# Proto3-schematic_v1.net
KiCad netlist of a schematic drawn in EAGLE
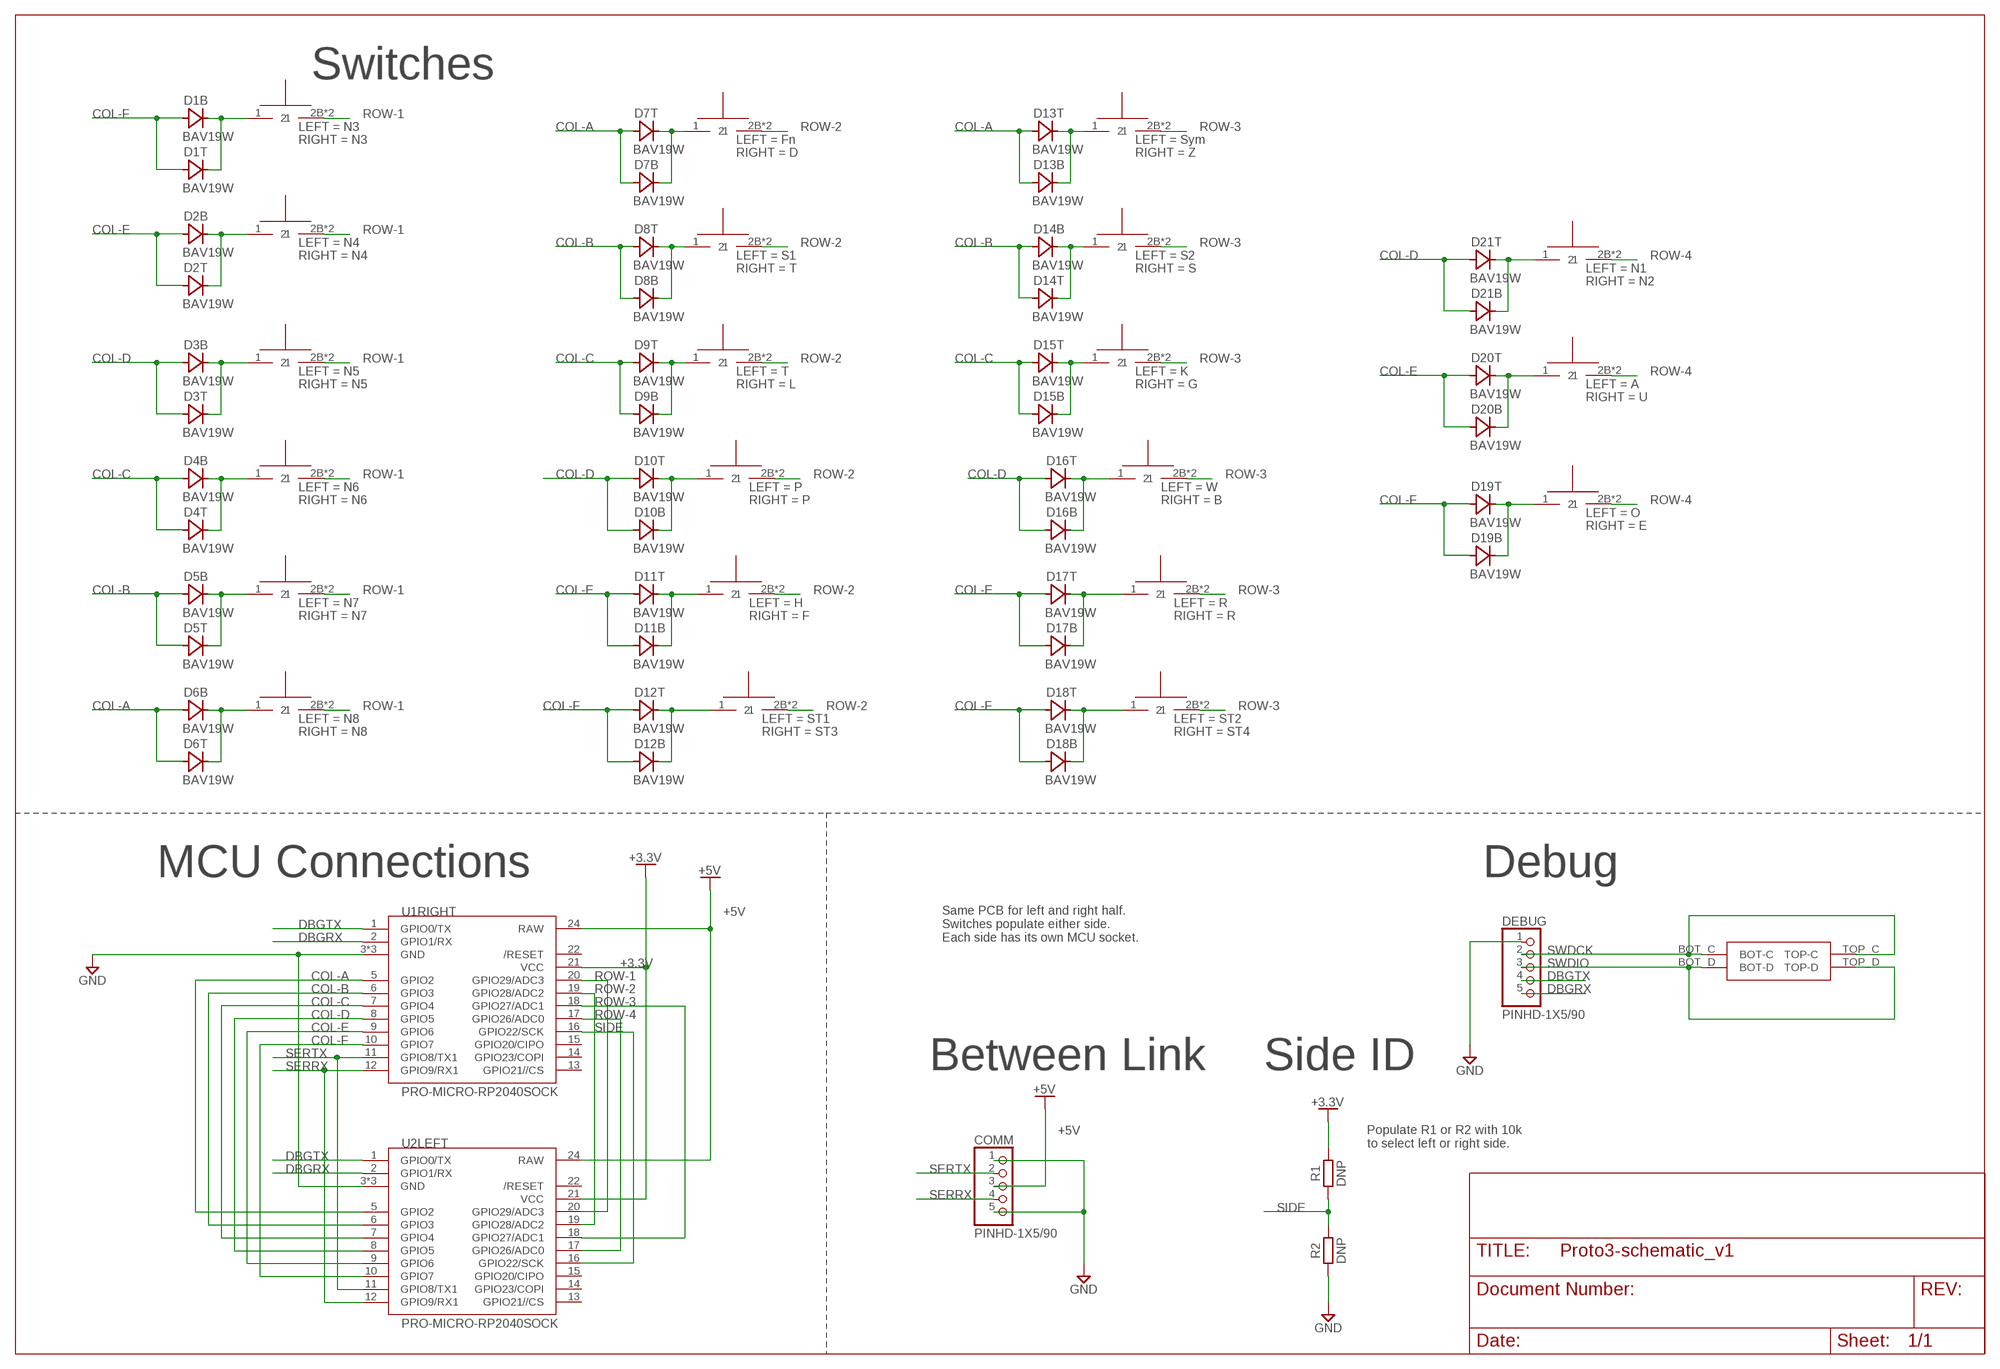
[diagram p0: schematic, sheet 1]

(export (version "E")
  (design (tool "Eeschema 10.0.6"))
  (components
    (comp (ref "COMM")
      (value "PINHD-1X5/90")
      (footprint "eagle-import:1X05_90")
      (libsource (lib "eagle-import") (part "PINHD-1X5/90"))
    )
    (comp (ref "D1B")
      (value "BAV19W")
      (footprint "eagle-import:SOD123")
      (libsource (lib "eagle-import") (part "BAV19W"))
    )
    (comp (ref "D1T")
      (value "BAV19W")
      (footprint "eagle-import:SOD123")
      (libsource (lib "eagle-import") (part "BAV19W"))
    )
    (comp (ref "D2B")
      (value "BAV19W")
      (footprint "eagle-import:SOD123")
      (libsource (lib "eagle-import") (part "BAV19W"))
    )
    (comp (ref "D2T")
      (value "BAV19W")
      (footprint "eagle-import:SOD123")
      (libsource (lib "eagle-import") (part "BAV19W"))
    )
    (comp (ref "D3B")
      (value "BAV19W")
      (footprint "eagle-import:SOD123")
      (libsource (lib "eagle-import") (part "BAV19W"))
    )
    (comp (ref "D3T")
      (value "BAV19W")
      (footprint "eagle-import:SOD123")
      (libsource (lib "eagle-import") (part "BAV19W"))
    )
    (comp (ref "D4B")
      (value "BAV19W")
      (footprint "eagle-import:SOD123")
      (libsource (lib "eagle-import") (part "BAV19W"))
    )
    (comp (ref "D4T")
      (value "BAV19W")
      (footprint "eagle-import:SOD123")
      (libsource (lib "eagle-import") (part "BAV19W"))
    )
    (comp (ref "D5B")
      (value "BAV19W")
      (footprint "eagle-import:SOD123")
      (libsource (lib "eagle-import") (part "BAV19W"))
    )
    (comp (ref "D5T")
      (value "BAV19W")
      (footprint "eagle-import:SOD123")
      (libsource (lib "eagle-import") (part "BAV19W"))
    )
    (comp (ref "D6B")
      (value "BAV19W")
      (footprint "eagle-import:SOD123")
      (libsource (lib "eagle-import") (part "BAV19W"))
    )
    (comp (ref "D6T")
      (value "BAV19W")
      (footprint "eagle-import:SOD123")
      (libsource (lib "eagle-import") (part "BAV19W"))
    )
    (comp (ref "D7B")
      (value "BAV19W")
      (footprint "eagle-import:SOD123")
      (libsource (lib "eagle-import") (part "BAV19W"))
    )
    (comp (ref "D7T")
      (value "BAV19W")
      (footprint "eagle-import:SOD123")
      (libsource (lib "eagle-import") (part "BAV19W"))
    )
    (comp (ref "D8B")
      (value "BAV19W")
      (footprint "eagle-import:SOD123")
      (libsource (lib "eagle-import") (part "BAV19W"))
    )
    (comp (ref "D8T")
      (value "BAV19W")
      (footprint "eagle-import:SOD123")
      (libsource (lib "eagle-import") (part "BAV19W"))
    )
    (comp (ref "D9B")
      (value "BAV19W")
      (footprint "eagle-import:SOD123")
      (libsource (lib "eagle-import") (part "BAV19W"))
    )
    (comp (ref "D9T")
      (value "BAV19W")
      (footprint "eagle-import:SOD123")
      (libsource (lib "eagle-import") (part "BAV19W"))
    )
    (comp (ref "D10B")
      (value "BAV19W")
      (footprint "eagle-import:SOD123")
      (libsource (lib "eagle-import") (part "BAV19W"))
    )
    (comp (ref "D10T")
      (value "BAV19W")
      (footprint "eagle-import:SOD123")
      (libsource (lib "eagle-import") (part "BAV19W"))
    )
    (comp (ref "D11B")
      (value "BAV19W")
      (footprint "eagle-import:SOD123")
      (libsource (lib "eagle-import") (part "BAV19W"))
    )
    (comp (ref "D11T")
      (value "BAV19W")
      (footprint "eagle-import:SOD123")
      (libsource (lib "eagle-import") (part "BAV19W"))
    )
    (comp (ref "D12B")
      (value "BAV19W")
      (footprint "eagle-import:SOD123")
      (libsource (lib "eagle-import") (part "BAV19W"))
    )
    (comp (ref "D12T")
      (value "BAV19W")
      (footprint "eagle-import:SOD123")
      (libsource (lib "eagle-import") (part "BAV19W"))
    )
    (comp (ref "D13B")
      (value "BAV19W")
      (footprint "eagle-import:SOD123")
      (libsource (lib "eagle-import") (part "BAV19W"))
    )
    (comp (ref "D13T")
      (value "BAV19W")
      (footprint "eagle-import:SOD123")
      (libsource (lib "eagle-import") (part "BAV19W"))
    )
    (comp (ref "D14B")
      (value "BAV19W")
      (footprint "eagle-import:SOD123")
      (libsource (lib "eagle-import") (part "BAV19W"))
    )
    (comp (ref "D14T")
      (value "BAV19W")
      (footprint "eagle-import:SOD123")
      (libsource (lib "eagle-import") (part "BAV19W"))
    )
    (comp (ref "D15B")
      (value "BAV19W")
      (footprint "eagle-import:SOD123")
      (libsource (lib "eagle-import") (part "BAV19W"))
    )
    (comp (ref "D15T")
      (value "BAV19W")
      (footprint "eagle-import:SOD123")
      (libsource (lib "eagle-import") (part "BAV19W"))
    )
    (comp (ref "D16B")
      (value "BAV19W")
      (footprint "eagle-import:SOD123")
      (libsource (lib "eagle-import") (part "BAV19W"))
    )
    (comp (ref "D16T")
      (value "BAV19W")
      (footprint "eagle-import:SOD123")
      (libsource (lib "eagle-import") (part "BAV19W"))
    )
    (comp (ref "D17B")
      (value "BAV19W")
      (footprint "eagle-import:SOD123")
      (libsource (lib "eagle-import") (part "BAV19W"))
    )
    (comp (ref "D17T")
      (value "BAV19W")
      (footprint "eagle-import:SOD123")
      (libsource (lib "eagle-import") (part "BAV19W"))
    )
    (comp (ref "D18B")
      (value "BAV19W")
      (footprint "eagle-import:SOD123")
      (libsource (lib "eagle-import") (part "BAV19W"))
    )
    (comp (ref "D18T")
      (value "BAV19W")
      (footprint "eagle-import:SOD123")
      (libsource (lib "eagle-import") (part "BAV19W"))
    )
    (comp (ref "D19B")
      (value "BAV19W")
      (footprint "eagle-import:SOD123")
      (libsource (lib "eagle-import") (part "BAV19W"))
    )
    (comp (ref "D19T")
      (value "BAV19W")
      (footprint "eagle-import:SOD123")
      (libsource (lib "eagle-import") (part "BAV19W"))
    )
    (comp (ref "D20B")
      (value "BAV19W")
      (footprint "eagle-import:SOD123")
      (libsource (lib "eagle-import") (part "BAV19W"))
    )
    (comp (ref "D20T")
      (value "BAV19W")
      (footprint "eagle-import:SOD123")
      (libsource (lib "eagle-import") (part "BAV19W"))
    )
    (comp (ref "D21B")
      (value "BAV19W")
      (footprint "eagle-import:SOD123")
      (libsource (lib "eagle-import") (part "BAV19W"))
    )
    (comp (ref "D21T")
      (value "BAV19W")
      (footprint "eagle-import:SOD123")
      (libsource (lib "eagle-import") (part "BAV19W"))
    )
    (comp (ref "DEBUG")
      (value "PINHD-1X5/90")
      (footprint "eagle-import:1X05_90")
      (libsource (lib "eagle-import") (part "PINHD-1X5/90"))
    )
    (comp (ref "R1")
      (value "DNP")
      (footprint "eagle-import:RESAD724W46L381D178B")
      (libsource (lib "eagle-import") (part "RAXIAL-7.2MM-PITCH_"))
    )
    (comp (ref "R2")
      (value "DNP")
      (footprint "eagle-import:RESAD724W46L381D178B")
      (libsource (lib "eagle-import") (part "RAXIAL-7.2MM-PITCH_"))
    )
    (comp (ref "SW-LFN-RD")
      (value "PG1350-PINKA")
      (footprint "eagle-import:PG1350")
      (fields (field (name "LEFT") "Fn") (field (name "RIGHT") "D"))
      (libsource (lib "eagle-import") (part "PG1350-PINKA"))
    )
    (comp (ref "SW-LFN-RD1")
      (value "PG1350-PINKA")
      (footprint "eagle-import:PG1350")
      (fields (field (name "LEFT") "Sym") (field (name "RIGHT") "Z"))
      (libsource (lib "eagle-import") (part "PG1350-PINKA"))
    )
    (comp (ref "SW-LFN-RD2")
      (value "PG1350-PINKA")
      (footprint "eagle-import:PG1350")
      (fields (field (name "LEFT") "S1") (field (name "RIGHT") "T"))
      (libsource (lib "eagle-import") (part "PG1350-PINKA"))
    )
    (comp (ref "SW-LFN-RD3")
      (value "PG1350-PINKA")
      (footprint "eagle-import:PG1350")
      (fields (field (name "LEFT") "S2") (field (name "RIGHT") "S"))
      (libsource (lib "eagle-import") (part "PG1350-PINKA"))
    )
    (comp (ref "SW-LFN-RD4")
      (value "PG1350-PINKA")
      (footprint "eagle-import:PG1350")
      (fields (field (name "LEFT") "T") (field (name "RIGHT") "L"))
      (libsource (lib "eagle-import") (part "PG1350-PINKA"))
    )
    (comp (ref "SW-LFN-RD5")
      (value "PG1350-PINKA")
      (footprint "eagle-import:PG1350")
      (fields (field (name "LEFT") "K") (field (name "RIGHT") "G"))
      (libsource (lib "eagle-import") (part "PG1350-PINKA"))
    )
    (comp (ref "SW-LFN-RD6")
      (value "PG1350-PINKA")
      (footprint "eagle-import:PG1350")
      (fields (field (name "LEFT") "P") (field (name "RIGHT") "P"))
      (libsource (lib "eagle-import") (part "PG1350-PINKA"))
    )
    (comp (ref "SW-LFN-RD7")
      (value "PG1350-PINKA")
      (footprint "eagle-import:PG1350")
      (fields (field (name "LEFT") "W") (field (name "RIGHT") "B"))
      (libsource (lib "eagle-import") (part "PG1350-PINKA"))
    )
    (comp (ref "SW-LFN-RD8")
      (value "PG1350-PINKA")
      (footprint "eagle-import:PG1350")
      (fields (field (name "LEFT") "H") (field (name "RIGHT") "F"))
      (libsource (lib "eagle-import") (part "PG1350-PINKA"))
    )
    (comp (ref "SW-LFN-RD9")
      (value "PG1350-PINKA")
      (footprint "eagle-import:PG1350")
      (fields (field (name "LEFT") "R") (field (name "RIGHT") "R"))
      (libsource (lib "eagle-import") (part "PG1350-PINKA"))
    )
    (comp (ref "SW-LFN-RD10")
      (value "PG1350-PINKA")
      (footprint "eagle-import:PG1350")
      (fields (field (name "LEFT") "ST1") (field (name "RIGHT") "ST3"))
      (libsource (lib "eagle-import") (part "PG1350-PINKA"))
    )
    (comp (ref "SW-LFN-RD11")
      (value "PG1350-PINKA")
      (footprint "eagle-import:PG1350")
      (fields (field (name "LEFT") "ST2") (field (name "RIGHT") "ST4"))
      (libsource (lib "eagle-import") (part "PG1350-PINKA"))
    )
    (comp (ref "SW-LFN-RD12")
      (value "PG1350-PINKA")
      (footprint "eagle-import:PG1350")
      (fields (field (name "LEFT") "N1") (field (name "RIGHT") "N2"))
      (libsource (lib "eagle-import") (part "PG1350-PINKA"))
    )
    (comp (ref "SW-LFN-RD13")
      (value "PG1350-PINKA")
      (footprint "eagle-import:PG1350")
      (fields (field (name "LEFT") "A") (field (name "RIGHT") "U"))
      (libsource (lib "eagle-import") (part "PG1350-PINKA"))
    )
    (comp (ref "SW-LFN-RD14")
      (value "PG1350-PINKA")
      (footprint "eagle-import:PG1350")
      (fields (field (name "LEFT") "O") (field (name "RIGHT") "E"))
      (libsource (lib "eagle-import") (part "PG1350-PINKA"))
    )
    (comp (ref "SW-LFN-RD15")
      (value "PG1350-PINKA")
      (footprint "eagle-import:PG1350")
      (fields (field (name "LEFT") "N8") (field (name "RIGHT") "N8"))
      (libsource (lib "eagle-import") (part "PG1350-PINKA"))
    )
    (comp (ref "SW-LFN-RD16")
      (value "PG1350-PINKA")
      (footprint "eagle-import:PG1350")
      (fields (field (name "LEFT") "N7") (field (name "RIGHT") "N7"))
      (libsource (lib "eagle-import") (part "PG1350-PINKA"))
    )
    (comp (ref "SW-LFN-RD17")
      (value "PG1350-PINKA")
      (footprint "eagle-import:PG1350")
      (fields (field (name "LEFT") "N6") (field (name "RIGHT") "N6"))
      (libsource (lib "eagle-import") (part "PG1350-PINKA"))
    )
    (comp (ref "SW-LFN-RD18")
      (value "PG1350-PINKA")
      (footprint "eagle-import:PG1350")
      (fields (field (name "LEFT") "N5") (field (name "RIGHT") "N5"))
      (libsource (lib "eagle-import") (part "PG1350-PINKA"))
    )
    (comp (ref "SW-LFN-RD19")
      (value "PG1350-PINKA")
      (footprint "eagle-import:PG1350")
      (fields (field (name "LEFT") "N4") (field (name "RIGHT") "N4"))
      (libsource (lib "eagle-import") (part "PG1350-PINKA"))
    )
    (comp (ref "SW-LFN-RD20")
      (value "PG1350-PINKA")
      (footprint "eagle-import:PG1350")
      (fields (field (name "LEFT") "N3") (field (name "RIGHT") "N3"))
      (libsource (lib "eagle-import") (part "PG1350-PINKA"))
    )
    (comp (ref "U$3")
      (value "SWD-TP-HEADER")
      (footprint "eagle-import:SWD-TP-HEADER")
      (libsource (lib "eagle-import") (part "SWD-TP-HEADER"))
    )
    (comp (ref "U1RIGHT")
      (value "PRO-MICRO-RP2040SOCK")
      (footprint "eagle-import:PRO-MICRO-RP2040-SOCKETED")
      (libsource (lib "eagle-import") (part "PRO-MICRO-RP2040SOCK"))
    )
    (comp (ref "U2LEFT")
      (value "PRO-MICRO-RP2040SOCK")
      (footprint "eagle-import:PRO-MICRO-RP2040-SOCKETED")
      (libsource (lib "eagle-import") (part "PRO-MICRO-RP2040SOCK"))
    )
  )
  (nets
    (net (code "1") (name "+3.3V") (class "Default")
      (node (ref "R1") (pin "2") (pinfunction "2_2") (pintype "passive"))
      (node (ref "U1RIGHT") (pin "21") (pinfunction "VCC_21") (pintype "power_in"))
      (node (ref "U2LEFT") (pin "21") (pinfunction "VCC_21") (pintype "power_in"))
    )
    (net (code "2") (name "+5V") (class "Default")
      (node (ref "COMM") (pin "3") (pinfunction "3_3") (pintype "passive"))
      (node (ref "U1RIGHT") (pin "24") (pinfunction "RAW_24") (pintype "power_in"))
      (node (ref "U2LEFT") (pin "24") (pinfunction "RAW_24") (pintype "power_in"))
    )
    (net (code "3") (name "/COL-A") (class "Default")
      (node (ref "D13B") (pin "A") (pinfunction "A_A") (pintype "passive"))
      (node (ref "D13T") (pin "A") (pinfunction "A_A") (pintype "passive"))
      (node (ref "D6B") (pin "A") (pinfunction "A_A") (pintype "passive"))
      (node (ref "D6T") (pin "A") (pinfunction "A_A") (pintype "passive"))
      (node (ref "D7B") (pin "A") (pinfunction "A_A") (pintype "passive"))
      (node (ref "D7T") (pin "A") (pinfunction "A_A") (pintype "passive"))
      (node (ref "U1RIGHT") (pin "5") (pinfunction "GPIO2_5") (pintype "bidirectional"))
      (node (ref "U2LEFT") (pin "5") (pinfunction "GPIO2_5") (pintype "bidirectional"))
    )
    (net (code "4") (name "/COL-B") (class "Default")
      (node (ref "D14B") (pin "A") (pinfunction "A_A") (pintype "passive"))
      (node (ref "D14T") (pin "A") (pinfunction "A_A") (pintype "passive"))
      (node (ref "D5B") (pin "A") (pinfunction "A_A") (pintype "passive"))
      (node (ref "D5T") (pin "A") (pinfunction "A_A") (pintype "passive"))
      (node (ref "D8B") (pin "A") (pinfunction "A_A") (pintype "passive"))
      (node (ref "D8T") (pin "A") (pinfunction "A_A") (pintype "passive"))
      (node (ref "U1RIGHT") (pin "6") (pinfunction "GPIO3_6") (pintype "bidirectional"))
      (node (ref "U2LEFT") (pin "6") (pinfunction "GPIO3_6") (pintype "bidirectional"))
    )
    (net (code "5") (name "/COL-C") (class "Default")
      (node (ref "D15B") (pin "A") (pinfunction "A_A") (pintype "passive"))
      (node (ref "D15T") (pin "A") (pinfunction "A_A") (pintype "passive"))
      (node (ref "D4B") (pin "A") (pinfunction "A_A") (pintype "passive"))
      (node (ref "D4T") (pin "A") (pinfunction "A_A") (pintype "passive"))
      (node (ref "D9B") (pin "A") (pinfunction "A_A") (pintype "passive"))
      (node (ref "D9T") (pin "A") (pinfunction "A_A") (pintype "passive"))
      (node (ref "U1RIGHT") (pin "7") (pinfunction "GPIO4_7") (pintype "bidirectional"))
      (node (ref "U2LEFT") (pin "7") (pinfunction "GPIO4_7") (pintype "bidirectional"))
    )
    (net (code "6") (name "/COL-D") (class "Default")
      (node (ref "D10B") (pin "A") (pinfunction "A_A") (pintype "passive"))
      (node (ref "D10T") (pin "A") (pinfunction "A_A") (pintype "passive"))
      (node (ref "D16B") (pin "A") (pinfunction "A_A") (pintype "passive"))
      (node (ref "D16T") (pin "A") (pinfunction "A_A") (pintype "passive"))
      (node (ref "D21B") (pin "A") (pinfunction "A_A") (pintype "passive"))
      (node (ref "D21T") (pin "A") (pinfunction "A_A") (pintype "passive"))
      (node (ref "D3B") (pin "A") (pinfunction "A_A") (pintype "passive"))
      (node (ref "D3T") (pin "A") (pinfunction "A_A") (pintype "passive"))
      (node (ref "U1RIGHT") (pin "8") (pinfunction "GPIO5_8") (pintype "bidirectional"))
      (node (ref "U2LEFT") (pin "8") (pinfunction "GPIO5_8") (pintype "bidirectional"))
    )
    (net (code "7") (name "/COL-E") (class "Default")
      (node (ref "D11B") (pin "A") (pinfunction "A_A") (pintype "passive"))
      (node (ref "D11T") (pin "A") (pinfunction "A_A") (pintype "passive"))
      (node (ref "D17B") (pin "A") (pinfunction "A_A") (pintype "passive"))
      (node (ref "D17T") (pin "A") (pinfunction "A_A") (pintype "passive"))
      (node (ref "D20B") (pin "A") (pinfunction "A_A") (pintype "passive"))
      (node (ref "D20T") (pin "A") (pinfunction "A_A") (pintype "passive"))
      (node (ref "D2B") (pin "A") (pinfunction "A_A") (pintype "passive"))
      (node (ref "D2T") (pin "A") (pinfunction "A_A") (pintype "passive"))
      (node (ref "U1RIGHT") (pin "9") (pinfunction "GPIO6_9") (pintype "bidirectional"))
      (node (ref "U2LEFT") (pin "9") (pinfunction "GPIO6_9") (pintype "bidirectional"))
    )
    (net (code "8") (name "/COL-F") (class "Default")
      (node (ref "D12B") (pin "A") (pinfunction "A_A") (pintype "passive"))
      (node (ref "D12T") (pin "A") (pinfunction "A_A") (pintype "passive"))
      (node (ref "D18B") (pin "A") (pinfunction "A_A") (pintype "passive"))
      (node (ref "D18T") (pin "A") (pinfunction "A_A") (pintype "passive"))
      (node (ref "D19B") (pin "A") (pinfunction "A_A") (pintype "passive"))
      (node (ref "D19T") (pin "A") (pinfunction "A_A") (pintype "passive"))
      (node (ref "D1B") (pin "A") (pinfunction "A_A") (pintype "passive"))
      (node (ref "D1T") (pin "A") (pinfunction "A_A") (pintype "passive"))
      (node (ref "U1RIGHT") (pin "10") (pinfunction "GPIO7_10") (pintype "bidirectional"))
      (node (ref "U2LEFT") (pin "10") (pinfunction "GPIO7_10") (pintype "bidirectional"))
    )
    (net (code "9") (name "/DBGRX") (class "Default")
      (node (ref "DEBUG") (pin "5") (pinfunction "5_5") (pintype "passive"))
      (node (ref "U1RIGHT") (pin "2") (pinfunction "GPIO1/RX_2") (pintype "bidirectional"))
      (node (ref "U2LEFT") (pin "2") (pinfunction "GPIO1/RX_2") (pintype "bidirectional"))
    )
    (net (code "10") (name "/DBGTX") (class "Default")
      (node (ref "DEBUG") (pin "4") (pinfunction "4_4") (pintype "passive"))
      (node (ref "U1RIGHT") (pin "1") (pinfunction "GPIO0/TX_1") (pintype "bidirectional"))
      (node (ref "U2LEFT") (pin "1") (pinfunction "GPIO0/TX_1") (pintype "bidirectional"))
    )
    (net (code "11") (name "/ROW-1") (class "Default")
      (node (ref "SW-LFN-RD15") (pin "2B") (pinfunction "2_2B") (pintype "passive"))
      (node (ref "SW-LFN-RD15") (pin "2T") (pinfunction "2_2T") (pintype "passive"))
      (node (ref "SW-LFN-RD16") (pin "2B") (pinfunction "2_2B") (pintype "passive"))
      (node (ref "SW-LFN-RD16") (pin "2T") (pinfunction "2_2T") (pintype "passive"))
      (node (ref "SW-LFN-RD17") (pin "2B") (pinfunction "2_2B") (pintype "passive"))
      (node (ref "SW-LFN-RD17") (pin "2T") (pinfunction "2_2T") (pintype "passive"))
      (node (ref "SW-LFN-RD18") (pin "2B") (pinfunction "2_2B") (pintype "passive"))
      (node (ref "SW-LFN-RD18") (pin "2T") (pinfunction "2_2T") (pintype "passive"))
      (node (ref "SW-LFN-RD19") (pin "2B") (pinfunction "2_2B") (pintype "passive"))
      (node (ref "SW-LFN-RD19") (pin "2T") (pinfunction "2_2T") (pintype "passive"))
      (node (ref "SW-LFN-RD20") (pin "2B") (pinfunction "2_2B") (pintype "passive"))
      (node (ref "SW-LFN-RD20") (pin "2T") (pinfunction "2_2T") (pintype "passive"))
      (node (ref "U1RIGHT") (pin "20") (pinfunction "GPIO29/ADC3_20") (pintype "bidirectional"))
      (node (ref "U2LEFT") (pin "20") (pinfunction "GPIO29/ADC3_20") (pintype "bidirectional"))
    )
    (net (code "12") (name "/ROW-2") (class "Default")
      (node (ref "SW-LFN-RD") (pin "2B") (pinfunction "2_2B") (pintype "passive"))
      (node (ref "SW-LFN-RD") (pin "2T") (pinfunction "2_2T") (pintype "passive"))
      (node (ref "SW-LFN-RD10") (pin "2B") (pinfunction "2_2B") (pintype "passive"))
      (node (ref "SW-LFN-RD10") (pin "2T") (pinfunction "2_2T") (pintype "passive"))
      (node (ref "SW-LFN-RD2") (pin "2B") (pinfunction "2_2B") (pintype "passive"))
      (node (ref "SW-LFN-RD2") (pin "2T") (pinfunction "2_2T") (pintype "passive"))
      (node (ref "SW-LFN-RD4") (pin "2B") (pinfunction "2_2B") (pintype "passive"))
      (node (ref "SW-LFN-RD4") (pin "2T") (pinfunction "2_2T") (pintype "passive"))
      (node (ref "SW-LFN-RD6") (pin "2B") (pinfunction "2_2B") (pintype "passive"))
      (node (ref "SW-LFN-RD6") (pin "2T") (pinfunction "2_2T") (pintype "passive"))
      (node (ref "SW-LFN-RD8") (pin "2B") (pinfunction "2_2B") (pintype "passive"))
      (node (ref "SW-LFN-RD8") (pin "2T") (pinfunction "2_2T") (pintype "passive"))
      (node (ref "U1RIGHT") (pin "19") (pinfunction "GPIO28/ADC2_19") (pintype "bidirectional"))
      (node (ref "U2LEFT") (pin "19") (pinfunction "GPIO28/ADC2_19") (pintype "bidirectional"))
    )
    (net (code "13") (name "/ROW-3") (class "Default")
      (node (ref "SW-LFN-RD1") (pin "2B") (pinfunction "2_2B") (pintype "passive"))
      (node (ref "SW-LFN-RD1") (pin "2T") (pinfunction "2_2T") (pintype "passive"))
      (node (ref "SW-LFN-RD11") (pin "2B") (pinfunction "2_2B") (pintype "passive"))
      (node (ref "SW-LFN-RD11") (pin "2T") (pinfunction "2_2T") (pintype "passive"))
      (node (ref "SW-LFN-RD3") (pin "2B") (pinfunction "2_2B") (pintype "passive"))
      (node (ref "SW-LFN-RD3") (pin "2T") (pinfunction "2_2T") (pintype "passive"))
      (node (ref "SW-LFN-RD5") (pin "2B") (pinfunction "2_2B") (pintype "passive"))
      (node (ref "SW-LFN-RD5") (pin "2T") (pinfunction "2_2T") (pintype "passive"))
      (node (ref "SW-LFN-RD7") (pin "2B") (pinfunction "2_2B") (pintype "passive"))
      (node (ref "SW-LFN-RD7") (pin "2T") (pinfunction "2_2T") (pintype "passive"))
      (node (ref "SW-LFN-RD9") (pin "2B") (pinfunction "2_2B") (pintype "passive"))
      (node (ref "SW-LFN-RD9") (pin "2T") (pinfunction "2_2T") (pintype "passive"))
      (node (ref "U1RIGHT") (pin "18") (pinfunction "GPIO27/ADC1_18") (pintype "bidirectional"))
      (node (ref "U2LEFT") (pin "18") (pinfunction "GPIO27/ADC1_18") (pintype "bidirectional"))
    )
    (net (code "14") (name "/ROW-4") (class "Default")
      (node (ref "SW-LFN-RD12") (pin "2B") (pinfunction "2_2B") (pintype "passive"))
      (node (ref "SW-LFN-RD12") (pin "2T") (pinfunction "2_2T") (pintype "passive"))
      (node (ref "SW-LFN-RD13") (pin "2B") (pinfunction "2_2B") (pintype "passive"))
      (node (ref "SW-LFN-RD13") (pin "2T") (pinfunction "2_2T") (pintype "passive"))
      (node (ref "SW-LFN-RD14") (pin "2B") (pinfunction "2_2B") (pintype "passive"))
      (node (ref "SW-LFN-RD14") (pin "2T") (pinfunction "2_2T") (pintype "passive"))
      (node (ref "U1RIGHT") (pin "17") (pinfunction "GPIO26/ADC0_17") (pintype "bidirectional"))
      (node (ref "U2LEFT") (pin "17") (pinfunction "GPIO26/ADC0_17") (pintype "bidirectional"))
    )
    (net (code "15") (name "/SERRX") (class "Default")
      (node (ref "COMM") (pin "4") (pinfunction "4_4") (pintype "passive"))
      (node (ref "U1RIGHT") (pin "12") (pinfunction "GPIO9/RX1_12") (pintype "bidirectional"))
      (node (ref "U2LEFT") (pin "12") (pinfunction "GPIO9/RX1_12") (pintype "bidirectional"))
    )
    (net (code "16") (name "/SERTX") (class "Default")
      (node (ref "COMM") (pin "2") (pinfunction "2_2") (pintype "passive"))
      (node (ref "U1RIGHT") (pin "11") (pinfunction "GPIO8/TX1_11") (pintype "bidirectional"))
      (node (ref "U2LEFT") (pin "11") (pinfunction "GPIO8/TX1_11") (pintype "bidirectional"))
    )
    (net (code "17") (name "/SIDE") (class "Default")
      (node (ref "R1") (pin "1") (pinfunction "1_1") (pintype "passive"))
      (node (ref "R2") (pin "2") (pinfunction "2_2") (pintype "passive"))
      (node (ref "U1RIGHT") (pin "16") (pinfunction "GPIO22/SCK_16") (pintype "bidirectional"))
      (node (ref "U2LEFT") (pin "16") (pinfunction "GPIO22/SCK_16") (pintype "bidirectional"))
    )
    (net (code "18") (name "/SWDCK") (class "Default")
      (node (ref "DEBUG") (pin "2") (pinfunction "2_2") (pintype "passive"))
      (node (ref "U$3") (pin "BOT_C") (pinfunction "BOT-C_BOT_C") (pintype "bidirectional"))
      (node (ref "U$3") (pin "TOP_C") (pinfunction "TOP-C_TOP_C") (pintype "bidirectional"))
    )
    (net (code "19") (name "/SWDIO") (class "Default")
      (node (ref "DEBUG") (pin "3") (pinfunction "3_3") (pintype "passive"))
      (node (ref "U$3") (pin "BOT_D") (pinfunction "BOT-D_BOT_D") (pintype "bidirectional"))
      (node (ref "U$3") (pin "TOP_D") (pinfunction "TOP-D_TOP_D") (pintype "bidirectional"))
    )
    (net (code "20") (name "GND") (class "Default")
      (node (ref "COMM") (pin "1") (pinfunction "1_1") (pintype "passive"))
      (node (ref "COMM") (pin "5") (pinfunction "5_5") (pintype "passive"))
      (node (ref "DEBUG") (pin "1") (pinfunction "1_1") (pintype "passive"))
      (node (ref "R2") (pin "1") (pinfunction "1_1") (pintype "passive"))
      (node (ref "U1RIGHT") (pin "23") (pinfunction "GND_23") (pintype "power_in"))
      (node (ref "U1RIGHT") (pin "3") (pinfunction "GND_3") (pintype "power_in"))
      (node (ref "U1RIGHT") (pin "4") (pinfunction "GND_4") (pintype "power_in"))
      (node (ref "U2LEFT") (pin "23") (pinfunction "GND_23") (pintype "power_in"))
      (node (ref "U2LEFT") (pin "3") (pinfunction "GND_3") (pintype "power_in"))
      (node (ref "U2LEFT") (pin "4") (pinfunction "GND_4") (pintype "power_in"))
    )
    (net (code "21") (name "Net-(D1B-PadC)") (class "Default")
      (node (ref "D1B") (pin "C") (pinfunction "C_C") (pintype "passive"))
      (node (ref "D1T") (pin "C") (pinfunction "C_C") (pintype "passive"))
      (node (ref "SW-LFN-RD20") (pin "1") (pinfunction "1_1") (pintype "passive"))
    )
    (net (code "22") (name "Net-(D2B-PadC)") (class "Default")
      (node (ref "D2B") (pin "C") (pinfunction "C_C") (pintype "passive"))
      (node (ref "D2T") (pin "C") (pinfunction "C_C") (pintype "passive"))
      (node (ref "SW-LFN-RD19") (pin "1") (pinfunction "1_1") (pintype "passive"))
    )
    (net (code "23") (name "Net-(D3B-PadC)") (class "Default")
      (node (ref "D3B") (pin "C") (pinfunction "C_C") (pintype "passive"))
      (node (ref "D3T") (pin "C") (pinfunction "C_C") (pintype "passive"))
      (node (ref "SW-LFN-RD18") (pin "1") (pinfunction "1_1") (pintype "passive"))
    )
    (net (code "24") (name "Net-(D4B-PadC)") (class "Default")
      (node (ref "D4B") (pin "C") (pinfunction "C_C") (pintype "passive"))
      (node (ref "D4T") (pin "C") (pinfunction "C_C") (pintype "passive"))
      (node (ref "SW-LFN-RD17") (pin "1") (pinfunction "1_1") (pintype "passive"))
    )
    (net (code "25") (name "Net-(D5B-PadC)") (class "Default")
      (node (ref "D5B") (pin "C") (pinfunction "C_C") (pintype "passive"))
      (node (ref "D5T") (pin "C") (pinfunction "C_C") (pintype "passive"))
      (node (ref "SW-LFN-RD16") (pin "1") (pinfunction "1_1") (pintype "passive"))
    )
    (net (code "26") (name "Net-(D6B-PadC)") (class "Default")
      (node (ref "D6B") (pin "C") (pinfunction "C_C") (pintype "passive"))
      (node (ref "D6T") (pin "C") (pinfunction "C_C") (pintype "passive"))
      (node (ref "SW-LFN-RD15") (pin "1") (pinfunction "1_1") (pintype "passive"))
    )
    (net (code "27") (name "Net-(D7B-PadC)") (class "Default")
      (node (ref "D7B") (pin "C") (pinfunction "C_C") (pintype "passive"))
      (node (ref "D7T") (pin "C") (pinfunction "C_C") (pintype "passive"))
      (node (ref "SW-LFN-RD") (pin "1") (pinfunction "1_1") (pintype "passive"))
    )
    (net (code "28") (name "Net-(D8B-PadC)") (class "Default")
      (node (ref "D8B") (pin "C") (pinfunction "C_C") (pintype "passive"))
      (node (ref "D8T") (pin "C") (pinfunction "C_C") (pintype "passive"))
      (node (ref "SW-LFN-RD2") (pin "1") (pinfunction "1_1") (pintype "passive"))
    )
    (net (code "29") (name "Net-(D9B-PadC)") (class "Default")
      (node (ref "D9B") (pin "C") (pinfunction "C_C") (pintype "passive"))
      (node (ref "D9T") (pin "C") (pinfunction "C_C") (pintype "passive"))
      (node (ref "SW-LFN-RD4") (pin "1") (pinfunction "1_1") (pintype "passive"))
    )
    (net (code "30") (name "Net-(D10B-PadC)") (class "Default")
      (node (ref "D10B") (pin "C") (pinfunction "C_C") (pintype "passive"))
      (node (ref "D10T") (pin "C") (pinfunction "C_C") (pintype "passive"))
      (node (ref "SW-LFN-RD6") (pin "1") (pinfunction "1_1") (pintype "passive"))
    )
    (net (code "31") (name "Net-(D11B-PadC)") (class "Default")
      (node (ref "D11B") (pin "C") (pinfunction "C_C") (pintype "passive"))
      (node (ref "D11T") (pin "C") (pinfunction "C_C") (pintype "passive"))
      (node (ref "SW-LFN-RD8") (pin "1") (pinfunction "1_1") (pintype "passive"))
    )
    (net (code "32") (name "Net-(D12B-PadC)") (class "Default")
      (node (ref "D12B") (pin "C") (pinfunction "C_C") (pintype "passive"))
      (node (ref "D12T") (pin "C") (pinfunction "C_C") (pintype "passive"))
      (node (ref "SW-LFN-RD10") (pin "1") (pinfunction "1_1") (pintype "passive"))
    )
    (net (code "33") (name "Net-(D13B-PadC)") (class "Default")
      (node (ref "D13B") (pin "C") (pinfunction "C_C") (pintype "passive"))
      (node (ref "D13T") (pin "C") (pinfunction "C_C") (pintype "passive"))
      (node (ref "SW-LFN-RD1") (pin "1") (pinfunction "1_1") (pintype "passive"))
    )
    (net (code "34") (name "Net-(D14B-PadC)") (class "Default")
      (node (ref "D14B") (pin "C") (pinfunction "C_C") (pintype "passive"))
      (node (ref "D14T") (pin "C") (pinfunction "C_C") (pintype "passive"))
      (node (ref "SW-LFN-RD3") (pin "1") (pinfunction "1_1") (pintype "passive"))
    )
    (net (code "35") (name "Net-(D15B-PadC)") (class "Default")
      (node (ref "D15B") (pin "C") (pinfunction "C_C") (pintype "passive"))
      (node (ref "D15T") (pin "C") (pinfunction "C_C") (pintype "passive"))
      (node (ref "SW-LFN-RD5") (pin "1") (pinfunction "1_1") (pintype "passive"))
    )
    (net (code "36") (name "Net-(D16B-PadC)") (class "Default")
      (node (ref "D16B") (pin "C") (pinfunction "C_C") (pintype "passive"))
      (node (ref "D16T") (pin "C") (pinfunction "C_C") (pintype "passive"))
      (node (ref "SW-LFN-RD7") (pin "1") (pinfunction "1_1") (pintype "passive"))
    )
    (net (code "37") (name "Net-(D17B-PadC)") (class "Default")
      (node (ref "D17B") (pin "C") (pinfunction "C_C") (pintype "passive"))
      (node (ref "D17T") (pin "C") (pinfunction "C_C") (pintype "passive"))
      (node (ref "SW-LFN-RD9") (pin "1") (pinfunction "1_1") (pintype "passive"))
    )
    (net (code "38") (name "Net-(D18B-PadC)") (class "Default")
      (node (ref "D18B") (pin "C") (pinfunction "C_C") (pintype "passive"))
      (node (ref "D18T") (pin "C") (pinfunction "C_C") (pintype "passive"))
      (node (ref "SW-LFN-RD11") (pin "1") (pinfunction "1_1") (pintype "passive"))
    )
    (net (code "39") (name "Net-(D19B-PadC)") (class "Default")
      (node (ref "D19B") (pin "C") (pinfunction "C_C") (pintype "passive"))
      (node (ref "D19T") (pin "C") (pinfunction "C_C") (pintype "passive"))
      (node (ref "SW-LFN-RD14") (pin "1") (pinfunction "1_1") (pintype "passive"))
    )
    (net (code "40") (name "Net-(D20B-PadC)") (class "Default")
      (node (ref "D20B") (pin "C") (pinfunction "C_C") (pintype "passive"))
      (node (ref "D20T") (pin "C") (pinfunction "C_C") (pintype "passive"))
      (node (ref "SW-LFN-RD13") (pin "1") (pinfunction "1_1") (pintype "passive"))
    )
    (net (code "41") (name "Net-(D21B-PadC)") (class "Default")
      (node (ref "D21B") (pin "C") (pinfunction "C_C") (pintype "passive"))
      (node (ref "D21T") (pin "C") (pinfunction "C_C") (pintype "passive"))
      (node (ref "SW-LFN-RD12") (pin "1") (pinfunction "1_1") (pintype "passive"))
    )
    (net (code "42") (name "unconnected-(U1RIGHT-GPIO20{slash}CIPO-Pad15)") (class "Default")
      (node (ref "U1RIGHT") (pin "15") (pinfunction "GPIO20/CIPO_15") (pintype "bidirectional"))
    )
    (net (code "43") (name "unconnected-(U1RIGHT-GPIO21{slash}{slash}CS-Pad13)") (class "Default")
      (node (ref "U1RIGHT") (pin "13") (pinfunction "GPIO21//CS_13") (pintype "bidirectional"))
    )
    (net (code "44") (name "unconnected-(U1RIGHT-GPIO23{slash}COPI-Pad14)") (class "Default")
      (node (ref "U1RIGHT") (pin "14") (pinfunction "GPIO23/COPI_14") (pintype "bidirectional"))
    )
    (net (code "45") (name "unconnected-(U1RIGHT-{slash}RESET-Pad22)") (class "Default")
      (node (ref "U1RIGHT") (pin "22") (pinfunction "/RESET_22") (pintype "input"))
    )
    (net (code "46") (name "unconnected-(U2LEFT-GPIO20{slash}CIPO-Pad15)") (class "Default")
      (node (ref "U2LEFT") (pin "15") (pinfunction "GPIO20/CIPO_15") (pintype "bidirectional"))
    )
    (net (code "47") (name "unconnected-(U2LEFT-GPIO21{slash}{slash}CS-Pad13)") (class "Default")
      (node (ref "U2LEFT") (pin "13") (pinfunction "GPIO21//CS_13") (pintype "bidirectional"))
    )
    (net (code "48") (name "unconnected-(U2LEFT-GPIO23{slash}COPI-Pad14)") (class "Default")
      (node (ref "U2LEFT") (pin "14") (pinfunction "GPIO23/COPI_14") (pintype "bidirectional"))
    )
    (net (code "49") (name "unconnected-(U2LEFT-{slash}RESET-Pad22)") (class "Default")
      (node (ref "U2LEFT") (pin "22") (pinfunction "/RESET_22") (pintype "input"))
    )
  )
)
